# camera2.net
KiCad netlist of a schematic drawn in EAGLE
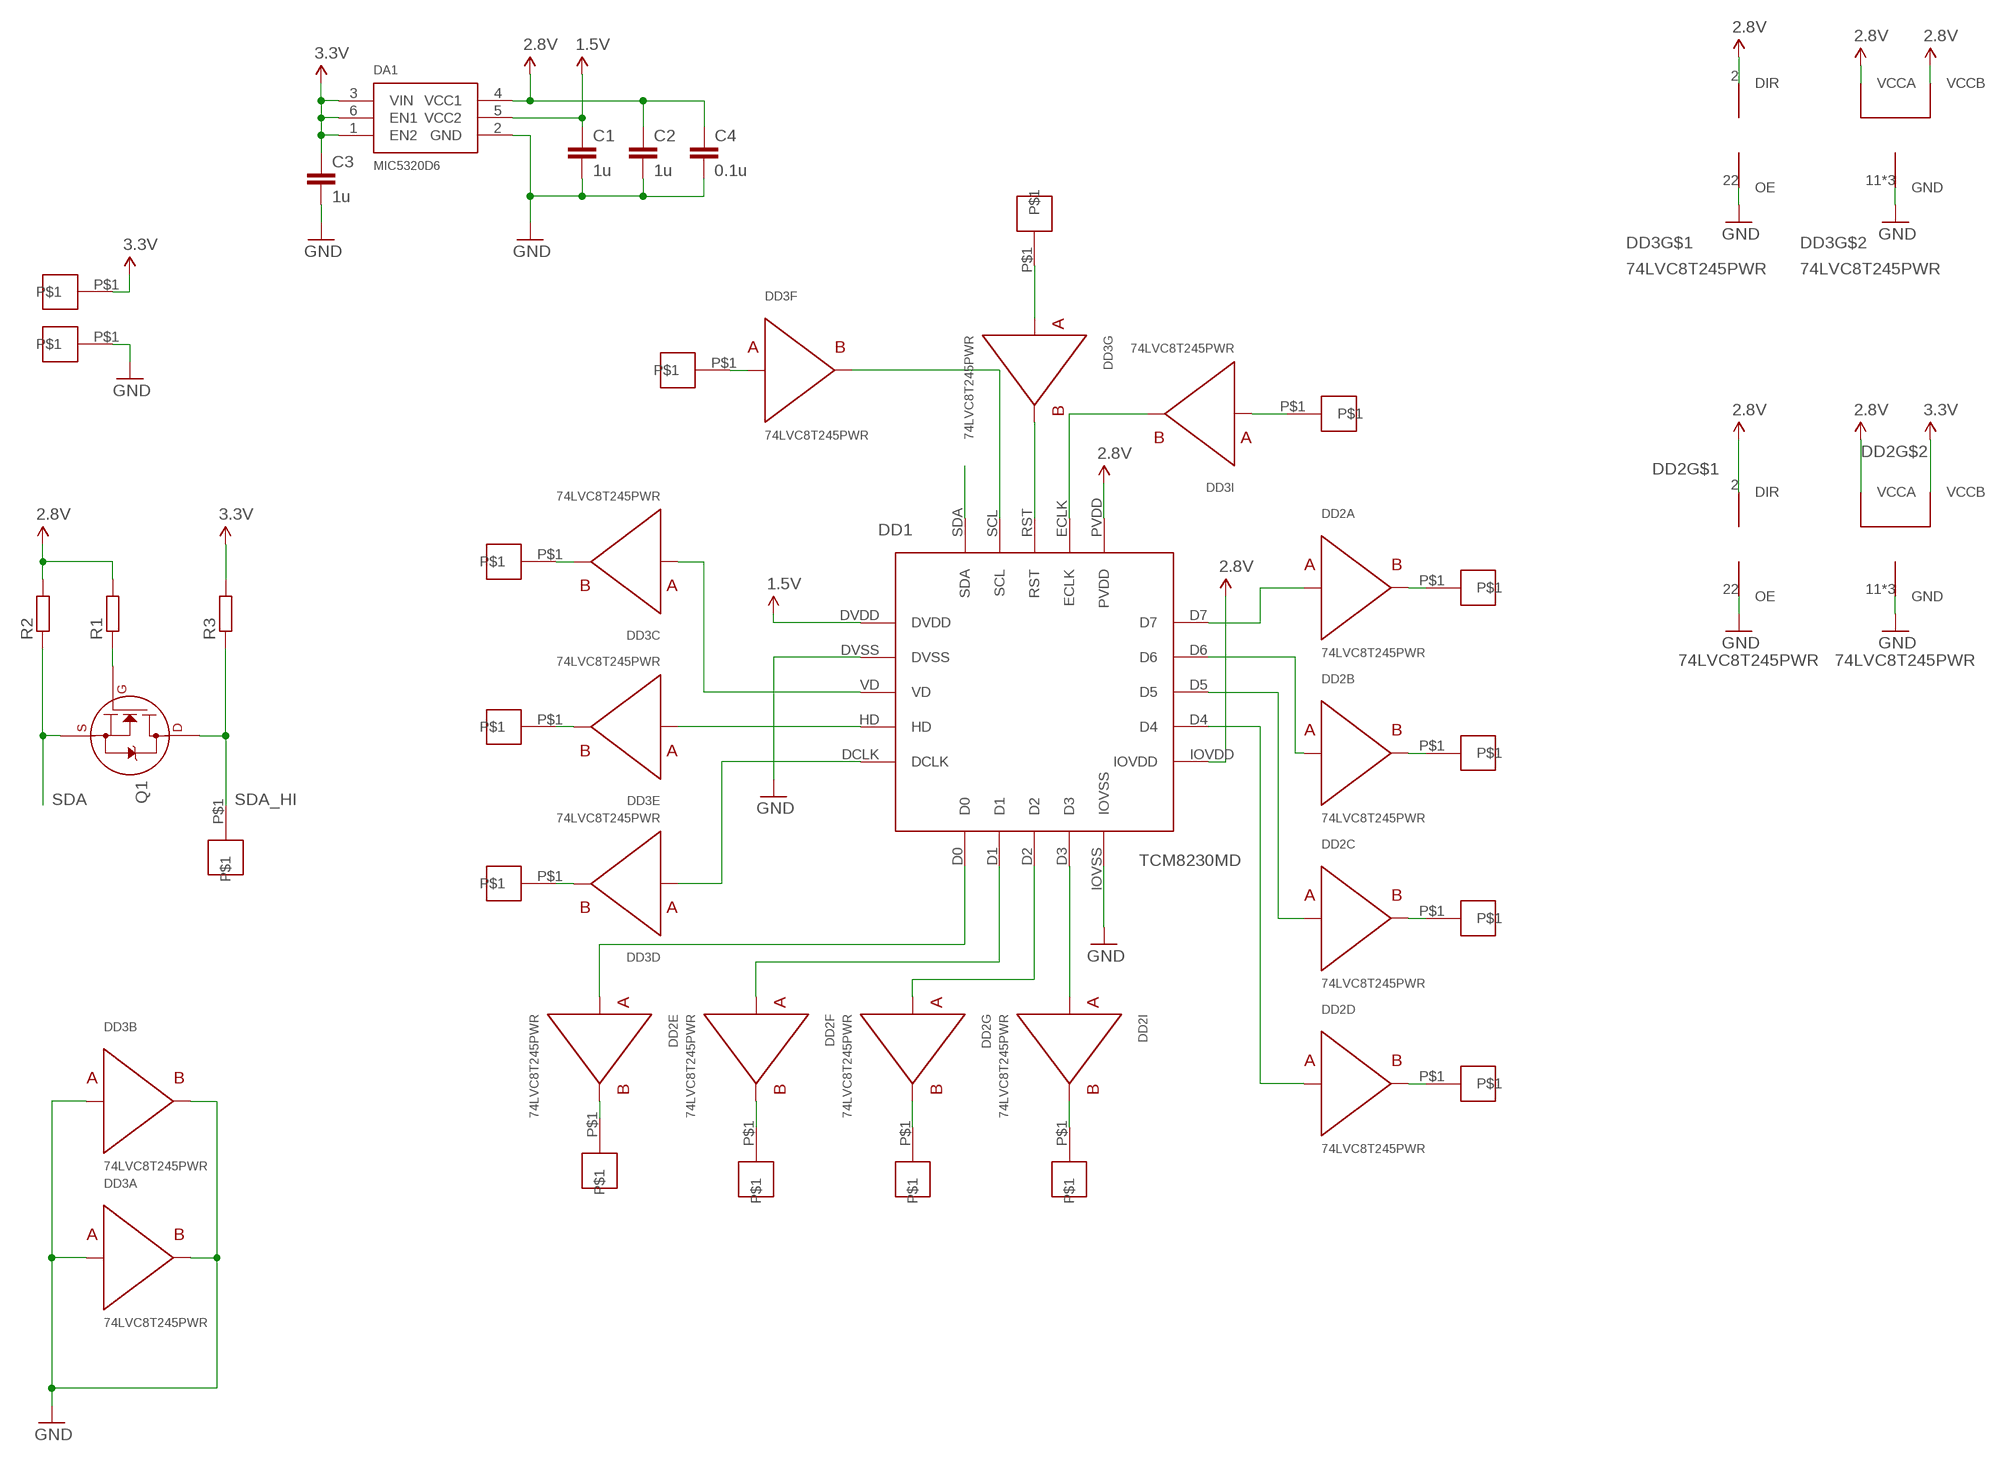
[diagram p0: schematic, sheet 1]

(export (version "E")
  (design (tool "Eeschema 10.0.6"))
  (components
    (comp (ref "C1")
      (value "1u")
      (footprint "eagle-import:C0603")
      (libsource (lib "eagle-import") (part "C-EUC0603"))
    )
    (comp (ref "C2")
      (value "1u")
      (footprint "eagle-import:C0603")
      (libsource (lib "eagle-import") (part "C-EUC0603"))
    )
    (comp (ref "C3")
      (value "1u")
      (footprint "eagle-import:C0603")
      (libsource (lib "eagle-import") (part "C-EUC0603"))
    )
    (comp (ref "C4")
      (value "0.1u")
      (footprint "eagle-import:C0603")
      (libsource (lib "eagle-import") (part "C-EUC0603"))
    )
    (comp (ref "DA1")
      (value "MIC5320D6")
      (footprint "eagle-import:SOT23-6")
      (libsource (lib "eagle-import") (part "MIC5320D6"))
    )
    (comp (ref "DD1")
      (value "TCM8230MD")
      (footprint "eagle-import:TCM8230MD")
      (libsource (lib "eagle-import") (part "TCM8230MD"))
    )
    (comp (ref "DD2")
      (value "74LVC8T245PWR")
      (footprint "eagle-import:TSSOP24")
      (libsource (lib "eagle-import") (part "74LVC8T245PWR"))
    )
    (comp (ref "DD3")
      (value "74LVC8T245PWR")
      (footprint "eagle-import:TSSOP24")
      (libsource (lib "eagle-import") (part "74LVC8T245PWR"))
    )
    (comp (ref "GND")
      (value "HOLE")
      (footprint "eagle-import:HOLE")
      (libsource (lib "eagle-import") (part "HOLE"))
    )
    (comp (ref "Q1")
      (value "2N7000_SOT23")
      (footprint "eagle-import:SOT-23")
      (libsource (lib "eagle-import") (part "2N700_SOT230"))
    )
    (comp (ref "R1")
      (value "R-EU_R0603")
      (footprint "eagle-import:R0603")
      (libsource (lib "eagle-import") (part "R-EU_R0603"))
    )
    (comp (ref "R2")
      (value "R-EU_R0603")
      (footprint "eagle-import:R0603")
      (libsource (lib "eagle-import") (part "R-EU_R0603"))
    )
    (comp (ref "R3")
      (value "R-EU_R0603")
      (footprint "eagle-import:R0603")
      (libsource (lib "eagle-import") (part "R-EU_R0603"))
    )
    (comp (ref "SDAC")
      (value "HOLE")
      (footprint "eagle-import:HOLE")
      (libsource (lib "eagle-import") (part "HOLE"))
    )
    (comp (ref "SDLC")
      (value "HOLE")
      (footprint "eagle-import:HOLE")
      (libsource (lib "eagle-import") (part "HOLE"))
    )
    (comp (ref "U$27")
      (value "HOLE")
      (footprint "eagle-import:HOLE")
      (libsource (lib "eagle-import") (part "HOLE"))
    )
    (comp (ref "U$30")
      (value "HOLE")
      (footprint "eagle-import:HOLE")
      (libsource (lib "eagle-import") (part "HOLE"))
    )
    (comp (ref "U$31")
      (value "HOLE")
      (footprint "eagle-import:HOLE")
      (libsource (lib "eagle-import") (part "HOLE"))
    )
    (comp (ref "U$32")
      (value "HOLE")
      (footprint "eagle-import:HOLE")
      (libsource (lib "eagle-import") (part "HOLE"))
    )
    (comp (ref "U$33")
      (value "HOLE")
      (footprint "eagle-import:HOLE")
      (libsource (lib "eagle-import") (part "HOLE"))
    )
    (comp (ref "U$34")
      (value "HOLE")
      (footprint "eagle-import:HOLE")
      (libsource (lib "eagle-import") (part "HOLE"))
    )
    (comp (ref "U$35")
      (value "HOLE")
      (footprint "eagle-import:HOLE")
      (libsource (lib "eagle-import") (part "HOLE"))
    )
    (comp (ref "U$36")
      (value "HOLE")
      (footprint "eagle-import:HOLE")
      (libsource (lib "eagle-import") (part "HOLE"))
    )
    (comp (ref "U$37")
      (value "HOLE")
      (footprint "eagle-import:HOLE")
      (libsource (lib "eagle-import") (part "HOLE"))
    )
    (comp (ref "U$38")
      (value "HOLE")
      (footprint "eagle-import:HOLE")
      (libsource (lib "eagle-import") (part "HOLE"))
    )
    (comp (ref "U$39")
      (value "HOLE")
      (footprint "eagle-import:HOLE")
      (libsource (lib "eagle-import") (part "HOLE"))
    )
    (comp (ref "U$40")
      (value "HOLE")
      (footprint "eagle-import:HOLE")
      (libsource (lib "eagle-import") (part "HOLE"))
    )
    (comp (ref "U$41")
      (value "HOLE")
      (footprint "eagle-import:HOLE")
      (libsource (lib "eagle-import") (part "HOLE"))
    )
    (comp (ref "VDD")
      (value "HOLE")
      (footprint "eagle-import:HOLE")
      (libsource (lib "eagle-import") (part "HOLE"))
    )
  )
  (nets
    (net (code "1") (name "/SDA") (class "Default")
      (node (ref "DD1") (pin "SDA") (pinfunction "SDA_SDA") (pintype "bidirectional"))
      (node (ref "Q1") (pin "2") (pinfunction "S_2") (pintype "bidirectional"))
      (node (ref "R2") (pin "1") (pinfunction "1_1") (pintype "passive"))
    )
    (net (code "2") (name "/SDA_HI") (class "Default")
      (node (ref "Q1") (pin "3") (pinfunction "D_3") (pintype "bidirectional"))
      (node (ref "R3") (pin "1") (pinfunction "1_1") (pintype "passive"))
      (node (ref "SDAC") (pin "P$1") (pinfunction "P$1_P$1") (pintype "bidirectional"))
    )
    (net (code "3") (name "1.5V") (class "Default")
      (node (ref "C1") (pin "1") (pinfunction "1_1") (pintype "passive"))
      (node (ref "DA1") (pin "5") (pinfunction "VCC2_5") (pintype "power_in"))
      (node (ref "DD1") (pin "DVDD") (pinfunction "DVDD_DVDD") (pintype "power_in"))
    )
    (net (code "4") (name "2.8V") (class "Default")
      (node (ref "C2") (pin "1") (pinfunction "1_1") (pintype "passive"))
      (node (ref "C4") (pin "1") (pinfunction "1_1") (pintype "passive"))
      (node (ref "DA1") (pin "4") (pinfunction "VCC1_4") (pintype "power_in"))
      (node (ref "DD1") (pin "IOVDD") (pinfunction "IOVDD_IOVDD") (pintype "power_in"))
      (node (ref "DD1") (pin "PVDD") (pinfunction "PVDD_PVDD") (pintype "power_in"))
      (node (ref "DD2") (pin "1") (pinfunction "VCCA_1") (pintype "power_in"))
      (node (ref "DD2") (pin "2") (pinfunction "DIR_2") (pintype "bidirectional"))
      (node (ref "DD3") (pin "1") (pinfunction "VCCA_1") (pintype "power_in"))
      (node (ref "DD3") (pin "2") (pinfunction "DIR_2") (pintype "bidirectional"))
      (node (ref "DD3") (pin "23") (pinfunction "VCCB_23") (pintype "power_in"))
      (node (ref "DD3") (pin "24") (pinfunction "VCCB_24") (pintype "power_in"))
      (node (ref "R1") (pin "2") (pinfunction "2_2") (pintype "passive"))
      (node (ref "R2") (pin "2") (pinfunction "2_2") (pintype "passive"))
    )
    (net (code "5") (name "3.3V") (class "Default")
      (node (ref "C3") (pin "1") (pinfunction "1_1") (pintype "passive"))
      (node (ref "DA1") (pin "1") (pinfunction "EN2_1") (pintype "input"))
      (node (ref "DA1") (pin "3") (pinfunction "VIN_3") (pintype "power_in"))
      (node (ref "DA1") (pin "6") (pinfunction "EN1_6") (pintype "input"))
      (node (ref "DD2") (pin "23") (pinfunction "VCCB_23") (pintype "power_in"))
      (node (ref "DD2") (pin "24") (pinfunction "VCCB_24") (pintype "power_in"))
      (node (ref "R3") (pin "2") (pinfunction "2_2") (pintype "passive"))
      (node (ref "VDD") (pin "P$1") (pinfunction "P$1_P$1") (pintype "bidirectional"))
    )
    (net (code "6") (name "GND") (class "Default")
      (node (ref "C1") (pin "2") (pinfunction "2_2") (pintype "passive"))
      (node (ref "C2") (pin "2") (pinfunction "2_2") (pintype "passive"))
      (node (ref "C3") (pin "2") (pinfunction "2_2") (pintype "passive"))
      (node (ref "C4") (pin "2") (pinfunction "2_2") (pintype "passive"))
      (node (ref "DA1") (pin "2") (pinfunction "GND_2") (pintype "power_in"))
      (node (ref "DD1") (pin "DVSS") (pinfunction "DVSS_DVSS") (pintype "power_in"))
      (node (ref "DD1") (pin "IOVSS") (pinfunction "IOVSS_IOVSS") (pintype "power_in"))
      (node (ref "DD2") (pin "11") (pinfunction "GND_11") (pintype "power_in"))
      (node (ref "DD2") (pin "12") (pinfunction "GND_12") (pintype "power_in"))
      (node (ref "DD2") (pin "13") (pinfunction "GND_13") (pintype "power_in"))
      (node (ref "DD2") (pin "22") (pinfunction "OE_22") (pintype "bidirectional"))
      (node (ref "DD3") (pin "11") (pinfunction "GND_11") (pintype "power_in"))
      (node (ref "DD3") (pin "12") (pinfunction "GND_12") (pintype "power_in"))
      (node (ref "DD3") (pin "13") (pinfunction "GND_13") (pintype "power_in"))
      (node (ref "DD3") (pin "20") (pinfunction "B1_20") (pintype "bidirectional"))
      (node (ref "DD3") (pin "21") (pinfunction "B1_21") (pintype "bidirectional"))
      (node (ref "DD3") (pin "22") (pinfunction "OE_22") (pintype "bidirectional"))
      (node (ref "DD3") (pin "3") (pinfunction "A1_3") (pintype "bidirectional"))
      (node (ref "DD3") (pin "4") (pinfunction "A1_4") (pintype "bidirectional"))
      (node (ref "GND") (pin "P$1") (pinfunction "P$1_P$1") (pintype "bidirectional"))
    )
    (net (code "7") (name "Net-(DD2A-A1)") (class "Default")
      (node (ref "DD1") (pin "D7") (pinfunction "D7_D7") (pintype "bidirectional"))
      (node (ref "DD2") (pin "3") (pinfunction "A1_3") (pintype "bidirectional"))
    )
    (net (code "8") (name "Net-(DD2A-B1)") (class "Default")
      (node (ref "DD2") (pin "21") (pinfunction "B1_21") (pintype "bidirectional"))
      (node (ref "U$33") (pin "P$1") (pinfunction "P$1_P$1") (pintype "bidirectional"))
    )
    (net (code "9") (name "Net-(DD2B-A1)") (class "Default")
      (node (ref "DD1") (pin "D6") (pinfunction "D6_D6") (pintype "bidirectional"))
      (node (ref "DD2") (pin "4") (pinfunction "A1_4") (pintype "bidirectional"))
    )
    (net (code "10") (name "Net-(DD2B-B1)") (class "Default")
      (node (ref "DD2") (pin "20") (pinfunction "B1_20") (pintype "bidirectional"))
      (node (ref "U$34") (pin "P$1") (pinfunction "P$1_P$1") (pintype "bidirectional"))
    )
    (net (code "11") (name "Net-(DD2C-A1)") (class "Default")
      (node (ref "DD1") (pin "D5") (pinfunction "D5_D5") (pintype "bidirectional"))
      (node (ref "DD2") (pin "5") (pinfunction "A1_5") (pintype "bidirectional"))
    )
    (net (code "12") (name "Net-(DD2C-B1)") (class "Default")
      (node (ref "DD2") (pin "19") (pinfunction "B1_19") (pintype "bidirectional"))
      (node (ref "U$35") (pin "P$1") (pinfunction "P$1_P$1") (pintype "bidirectional"))
    )
    (net (code "13") (name "Net-(DD2D-A1)") (class "Default")
      (node (ref "DD1") (pin "D4") (pinfunction "D4_D4") (pintype "bidirectional"))
      (node (ref "DD2") (pin "6") (pinfunction "A1_6") (pintype "bidirectional"))
    )
    (net (code "14") (name "Net-(DD2D-B1)") (class "Default")
      (node (ref "DD2") (pin "18") (pinfunction "B1_18") (pintype "bidirectional"))
      (node (ref "U$36") (pin "P$1") (pinfunction "P$1_P$1") (pintype "bidirectional"))
    )
    (net (code "15") (name "Net-(DD2E-A1)") (class "Default")
      (node (ref "DD1") (pin "D0") (pinfunction "D0_D0") (pintype "bidirectional"))
      (node (ref "DD2") (pin "7") (pinfunction "A1_7") (pintype "bidirectional"))
    )
    (net (code "16") (name "Net-(DD2E-B1)") (class "Default")
      (node (ref "DD2") (pin "17") (pinfunction "B1_17") (pintype "bidirectional"))
      (node (ref "U$32") (pin "P$1") (pinfunction "P$1_P$1") (pintype "bidirectional"))
    )
    (net (code "17") (name "Net-(DD2F-A1)") (class "Default")
      (node (ref "DD1") (pin "D1") (pinfunction "D1_D1") (pintype "bidirectional"))
      (node (ref "DD2") (pin "8") (pinfunction "A1_8") (pintype "bidirectional"))
    )
    (net (code "18") (name "Net-(DD2F-B1)") (class "Default")
      (node (ref "DD2") (pin "16") (pinfunction "B1_16") (pintype "bidirectional"))
      (node (ref "U$31") (pin "P$1") (pinfunction "P$1_P$1") (pintype "bidirectional"))
    )
    (net (code "19") (name "Net-(DD2G-A1)") (class "Default")
      (node (ref "DD1") (pin "D2") (pinfunction "D2_D2") (pintype "bidirectional"))
      (node (ref "DD2") (pin "9") (pinfunction "A1_9") (pintype "bidirectional"))
    )
    (net (code "20") (name "Net-(DD2G-B1)") (class "Default")
      (node (ref "DD2") (pin "15") (pinfunction "B1_15") (pintype "bidirectional"))
      (node (ref "U$30") (pin "P$1") (pinfunction "P$1_P$1") (pintype "bidirectional"))
    )
    (net (code "21") (name "Net-(DD2J-A1)") (class "Default")
      (node (ref "DD1") (pin "D3") (pinfunction "D3_D3") (pintype "bidirectional"))
      (node (ref "DD2") (pin "10") (pinfunction "A1_10") (pintype "bidirectional"))
    )
    (net (code "22") (name "Net-(DD2J-B1)") (class "Default")
      (node (ref "DD2") (pin "14") (pinfunction "B1_14") (pintype "bidirectional"))
      (node (ref "U$27") (pin "P$1") (pinfunction "P$1_P$1") (pintype "bidirectional"))
    )
    (net (code "23") (name "Net-(DD3C-A1)") (class "Default")
      (node (ref "DD1") (pin "VD") (pinfunction "VD_VD") (pintype "bidirectional"))
      (node (ref "DD3") (pin "5") (pinfunction "A1_5") (pintype "bidirectional"))
    )
    (net (code "24") (name "Net-(DD3C-B1)") (class "Default")
      (node (ref "DD3") (pin "19") (pinfunction "B1_19") (pintype "bidirectional"))
      (node (ref "U$37") (pin "P$1") (pinfunction "P$1_P$1") (pintype "bidirectional"))
    )
    (net (code "25") (name "Net-(DD3D-A1)") (class "Default")
      (node (ref "DD1") (pin "DCLK") (pinfunction "DCLK_DCLK") (pintype "bidirectional"))
      (node (ref "DD3") (pin "6") (pinfunction "A1_6") (pintype "bidirectional"))
    )
    (net (code "26") (name "Net-(DD3D-B1)") (class "Default")
      (node (ref "DD3") (pin "18") (pinfunction "B1_18") (pintype "bidirectional"))
      (node (ref "U$39") (pin "P$1") (pinfunction "P$1_P$1") (pintype "bidirectional"))
    )
    (net (code "27") (name "Net-(DD3E-A1)") (class "Default")
      (node (ref "DD1") (pin "HD") (pinfunction "HD_HD") (pintype "bidirectional"))
      (node (ref "DD3") (pin "7") (pinfunction "A1_7") (pintype "bidirectional"))
    )
    (net (code "28") (name "Net-(DD3E-B1)") (class "Default")
      (node (ref "DD3") (pin "17") (pinfunction "B1_17") (pintype "bidirectional"))
      (node (ref "U$38") (pin "P$1") (pinfunction "P$1_P$1") (pintype "bidirectional"))
    )
    (net (code "29") (name "Net-(DD3F-A1)") (class "Default")
      (node (ref "DD3") (pin "8") (pinfunction "A1_8") (pintype "bidirectional"))
      (node (ref "SDLC") (pin "P$1") (pinfunction "P$1_P$1") (pintype "bidirectional"))
    )
    (net (code "30") (name "Net-(DD3F-B1)") (class "Default")
      (node (ref "DD1") (pin "SCL") (pinfunction "SCL_SCL") (pintype "bidirectional"))
      (node (ref "DD3") (pin "16") (pinfunction "B1_16") (pintype "bidirectional"))
    )
    (net (code "31") (name "Net-(DD3G-A1)") (class "Default")
      (node (ref "DD3") (pin "9") (pinfunction "A1_9") (pintype "bidirectional"))
      (node (ref "U$40") (pin "P$1") (pinfunction "P$1_P$1") (pintype "bidirectional"))
    )
    (net (code "32") (name "Net-(DD3G-B1)") (class "Default")
      (node (ref "DD1") (pin "RST") (pinfunction "RST_RST") (pintype "bidirectional"))
      (node (ref "DD3") (pin "15") (pinfunction "B1_15") (pintype "bidirectional"))
    )
    (net (code "33") (name "Net-(DD3J-A1)") (class "Default")
      (node (ref "DD3") (pin "10") (pinfunction "A1_10") (pintype "bidirectional"))
      (node (ref "U$41") (pin "P$1") (pinfunction "P$1_P$1") (pintype "bidirectional"))
    )
    (net (code "34") (name "Net-(DD3J-B1)") (class "Default")
      (node (ref "DD1") (pin "ECLK") (pinfunction "ECLK_ECLK") (pintype "bidirectional"))
      (node (ref "DD3") (pin "14") (pinfunction "B1_14") (pintype "bidirectional"))
    )
    (net (code "35") (name "Net-(Q1-G)") (class "Default")
      (node (ref "Q1") (pin "1") (pinfunction "G_1") (pintype "tri_state"))
      (node (ref "R1") (pin "1") (pinfunction "1_1") (pintype "passive"))
    )
  )
)
